# drivers_SCH.net
KiCad netlist of a schematic drawn in Altium Designer
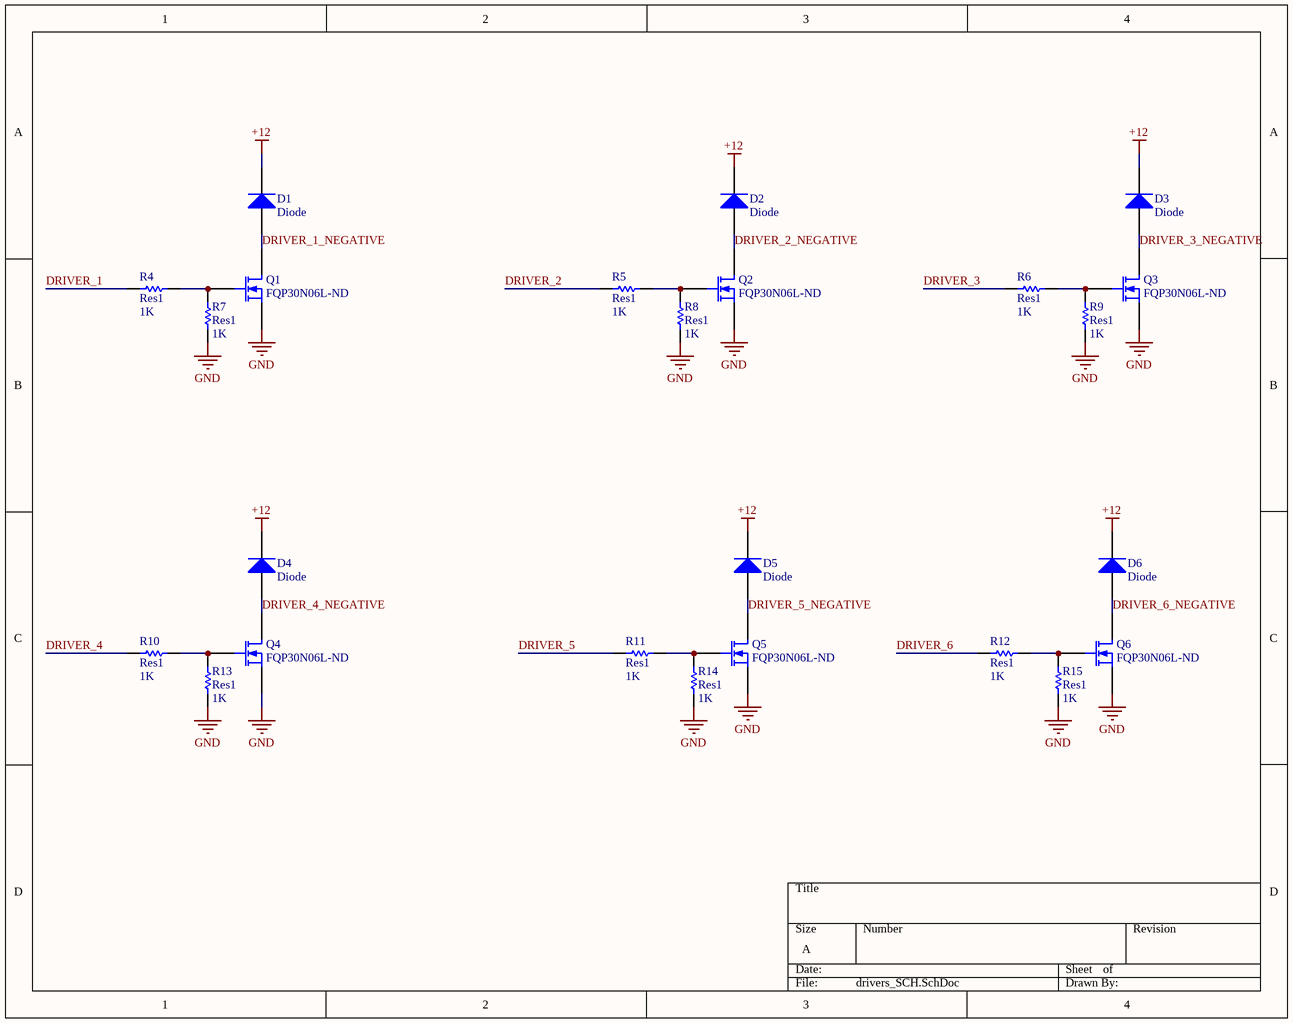
[diagram p0: drivers_SCH.SchDoc]

(export (version "E")
  (design (tool "Eeschema 10.0.6"))
  (components
    (comp (ref "D1")
      (value "Diode")
      (footprint "DIOC2012X06N")
      (description "Default Diode")
      (fields (field (name "PUBLISHER") "Altium Limited"))
      (libsource (lib "Miscellaneous Devices") (part "Diode"))
    )
    (comp (ref "D2")
      (value "Diode")
      (footprint "DIOC2012X06N")
      (description "Default Diode")
      (fields (field (name "PUBLISHER") "Altium Limited"))
      (libsource (lib "Miscellaneous Devices") (part "Diode"))
    )
    (comp (ref "D3")
      (value "Diode")
      (footprint "DIOC2012X06N")
      (description "Default Diode")
      (fields (field (name "PUBLISHER") "Altium Limited"))
      (libsource (lib "Miscellaneous Devices") (part "Diode"))
    )
    (comp (ref "D4")
      (value "Diode")
      (footprint "DIOC2012X06N")
      (description "Default Diode")
      (fields (field (name "PUBLISHER") "Altium Limited"))
      (libsource (lib "Miscellaneous Devices") (part "Diode"))
    )
    (comp (ref "D5")
      (value "Diode")
      (footprint "DIOC2012X06N")
      (description "Default Diode")
      (fields (field (name "PUBLISHER") "Altium Limited"))
      (libsource (lib "Miscellaneous Devices") (part "Diode"))
    )
    (comp (ref "D6")
      (value "Diode")
      (footprint "DIOC2012X06N")
      (description "Default Diode")
      (fields (field (name "PUBLISHER") "Altium Limited"))
      (libsource (lib "Miscellaneous Devices") (part "Diode"))
    )
    (comp (ref "Q1")
      (value "FQP30N06L-ND")
      (footprint "UA78M")
      (description "N-Channel MOSFET")
      (fields (field (name "PUBLISHER") "Altium Limited"))
      (libsource (lib "Miscellaneous Devices") (part "MOSFET-N"))
    )
    (comp (ref "Q2")
      (value "FQP30N06L-ND")
      (footprint "UA78M")
      (description "N-Channel MOSFET")
      (fields (field (name "PUBLISHER") "Altium Limited"))
      (libsource (lib "Miscellaneous Devices") (part "MOSFET-N"))
    )
    (comp (ref "Q3")
      (value "FQP30N06L-ND")
      (footprint "UA78M")
      (description "N-Channel MOSFET")
      (fields (field (name "PUBLISHER") "Altium Limited"))
      (libsource (lib "Miscellaneous Devices") (part "MOSFET-N"))
    )
    (comp (ref "Q4")
      (value "FQP30N06L-ND")
      (footprint "UA78M")
      (description "N-Channel MOSFET")
      (fields (field (name "PUBLISHER") "Altium Limited"))
      (libsource (lib "Miscellaneous Devices") (part "MOSFET-N"))
    )
    (comp (ref "Q5")
      (value "FQP30N06L-ND")
      (footprint "UA78M")
      (description "N-Channel MOSFET")
      (fields (field (name "PUBLISHER") "Altium Limited"))
      (libsource (lib "Miscellaneous Devices") (part "MOSFET-N"))
    )
    (comp (ref "Q6")
      (value "FQP30N06L-ND")
      (footprint "UA78M")
      (description "N-Channel MOSFET")
      (fields (field (name "PUBLISHER") "Altium Limited"))
      (libsource (lib "Miscellaneous Devices") (part "MOSFET-N"))
    )
    (comp (ref "R4")
      (value "Res1")
      (footprint "RESC_0805_2012")
      (description "Resistor")
      (fields (field (name "ALTIUM_VALUE") "1K") (field (name "PUBLISHER") "Altium Limited"))
      (libsource (lib "Miscellaneous Devices") (part "Res1"))
    )
    (comp (ref "R5")
      (value "Res1")
      (footprint "RESC_0805_2012")
      (description "Resistor")
      (fields (field (name "ALTIUM_VALUE") "1K") (field (name "PUBLISHER") "Altium Limited"))
      (libsource (lib "Miscellaneous Devices") (part "Res1"))
    )
    (comp (ref "R6")
      (value "Res1")
      (footprint "RESC_0805_2012")
      (description "Resistor")
      (fields (field (name "ALTIUM_VALUE") "1K") (field (name "PUBLISHER") "Altium Limited"))
      (libsource (lib "Miscellaneous Devices") (part "Res1"))
    )
    (comp (ref "R7")
      (value "Res1")
      (footprint "RESC_0805_2012")
      (description "Resistor")
      (fields (field (name "ALTIUM_VALUE") "1K") (field (name "PUBLISHER") "Altium Limited"))
      (libsource (lib "Miscellaneous Devices") (part "Res1"))
    )
    (comp (ref "R8")
      (value "Res1")
      (footprint "RESC_0805_2012")
      (description "Resistor")
      (fields (field (name "ALTIUM_VALUE") "1K") (field (name "PUBLISHER") "Altium Limited"))
      (libsource (lib "Miscellaneous Devices") (part "Res1"))
    )
    (comp (ref "R9")
      (value "Res1")
      (footprint "RESC_0805_2012")
      (description "Resistor")
      (fields (field (name "ALTIUM_VALUE") "1K") (field (name "PUBLISHER") "Altium Limited"))
      (libsource (lib "Miscellaneous Devices") (part "Res1"))
    )
    (comp (ref "R10")
      (value "Res1")
      (footprint "RESC_0805_2012")
      (description "Resistor")
      (fields (field (name "ALTIUM_VALUE") "1K") (field (name "PUBLISHER") "Altium Limited"))
      (libsource (lib "Miscellaneous Devices") (part "Res1"))
    )
    (comp (ref "R11")
      (value "Res1")
      (footprint "RESC_0805_2012")
      (description "Resistor")
      (fields (field (name "ALTIUM_VALUE") "1K") (field (name "PUBLISHER") "Altium Limited"))
      (libsource (lib "Miscellaneous Devices") (part "Res1"))
    )
    (comp (ref "R12")
      (value "Res1")
      (footprint "RESC_0805_2012")
      (description "Resistor")
      (fields (field (name "ALTIUM_VALUE") "1K") (field (name "PUBLISHER") "Altium Limited"))
      (libsource (lib "Miscellaneous Devices") (part "Res1"))
    )
    (comp (ref "R13")
      (value "Res1")
      (footprint "RESC_0805_2012")
      (description "Resistor")
      (fields (field (name "ALTIUM_VALUE") "1K") (field (name "PUBLISHER") "Altium Limited"))
      (libsource (lib "Miscellaneous Devices") (part "Res1"))
    )
    (comp (ref "R14")
      (value "Res1")
      (footprint "RESC_0805_2012")
      (description "Resistor")
      (fields (field (name "ALTIUM_VALUE") "1K") (field (name "PUBLISHER") "Altium Limited"))
      (libsource (lib "Miscellaneous Devices") (part "Res1"))
    )
    (comp (ref "R15")
      (value "Res1")
      (footprint "RESC_0805_2012")
      (description "Resistor")
      (fields (field (name "ALTIUM_VALUE") "1K") (field (name "PUBLISHER") "Altium Limited"))
      (libsource (lib "Miscellaneous Devices") (part "Res1"))
    )
  )
  (nets
    (net (code "1") (name "+12") (class "Default")
      (node (ref "D1") (pin "2") (pinfunction "K_2") (pintype "passive"))
      (node (ref "D2") (pin "2") (pinfunction "K_2") (pintype "passive"))
      (node (ref "D3") (pin "2") (pinfunction "K_2") (pintype "passive"))
      (node (ref "D4") (pin "2") (pinfunction "K_2") (pintype "passive"))
      (node (ref "D5") (pin "2") (pinfunction "K_2") (pintype "passive"))
      (node (ref "D6") (pin "2") (pinfunction "K_2") (pintype "passive"))
    )
    (net (code "2") (name "/DRIVER_1") (class "Default")
      (node (ref "R4") (pin "1") (pinfunction "1_1") (pintype "passive"))
    )
    (net (code "3") (name "/DRIVER_1_NEGATIVE") (class "Default")
      (node (ref "D1") (pin "1") (pinfunction "A_1") (pintype "passive"))
      (node (ref "Q1") (pin "2") (pinfunction "G_2") (pintype "passive"))
    )
    (net (code "4") (name "/DRIVER_2") (class "Default")
      (node (ref "R5") (pin "1") (pinfunction "1_1") (pintype "passive"))
    )
    (net (code "5") (name "/DRIVER_2_NEGATIVE") (class "Default")
      (node (ref "D2") (pin "1") (pinfunction "A_1") (pintype "passive"))
      (node (ref "Q2") (pin "2") (pinfunction "G_2") (pintype "passive"))
    )
    (net (code "6") (name "/DRIVER_3") (class "Default")
      (node (ref "R6") (pin "1") (pinfunction "1_1") (pintype "passive"))
    )
    (net (code "7") (name "/DRIVER_3_NEGATIVE") (class "Default")
      (node (ref "D3") (pin "1") (pinfunction "A_1") (pintype "passive"))
      (node (ref "Q3") (pin "2") (pinfunction "G_2") (pintype "passive"))
    )
    (net (code "8") (name "/DRIVER_4") (class "Default")
      (node (ref "R10") (pin "1") (pinfunction "1_1") (pintype "passive"))
    )
    (net (code "9") (name "/DRIVER_4_NEGATIVE") (class "Default")
      (node (ref "D4") (pin "1") (pinfunction "A_1") (pintype "passive"))
      (node (ref "Q4") (pin "2") (pinfunction "G_2") (pintype "passive"))
    )
    (net (code "10") (name "/DRIVER_5") (class "Default")
      (node (ref "R11") (pin "1") (pinfunction "1_1") (pintype "passive"))
    )
    (net (code "11") (name "/DRIVER_5_NEGATIVE") (class "Default")
      (node (ref "D5") (pin "1") (pinfunction "A_1") (pintype "passive"))
      (node (ref "Q5") (pin "2") (pinfunction "G_2") (pintype "passive"))
    )
    (net (code "12") (name "/DRIVER_6") (class "Default")
      (node (ref "R12") (pin "1") (pinfunction "1_1") (pintype "passive"))
    )
    (net (code "13") (name "/DRIVER_6_NEGATIVE") (class "Default")
      (node (ref "D6") (pin "1") (pinfunction "A_1") (pintype "passive"))
      (node (ref "Q6") (pin "2") (pinfunction "G_2") (pintype "passive"))
    )
    (net (code "14") (name "GND") (class "Default")
      (node (ref "Q1") (pin "3") (pinfunction "S_3") (pintype "passive"))
      (node (ref "Q2") (pin "3") (pinfunction "S_3") (pintype "passive"))
      (node (ref "Q3") (pin "3") (pinfunction "S_3") (pintype "passive"))
      (node (ref "Q4") (pin "3") (pinfunction "S_3") (pintype "passive"))
      (node (ref "Q5") (pin "3") (pinfunction "S_3") (pintype "passive"))
      (node (ref "Q6") (pin "3") (pinfunction "S_3") (pintype "passive"))
      (node (ref "R13") (pin "1") (pinfunction "1_1") (pintype "passive"))
      (node (ref "R14") (pin "1") (pinfunction "1_1") (pintype "passive"))
      (node (ref "R15") (pin "1") (pinfunction "1_1") (pintype "passive"))
      (node (ref "R7") (pin "1") (pinfunction "1_1") (pintype "passive"))
      (node (ref "R8") (pin "1") (pinfunction "1_1") (pintype "passive"))
      (node (ref "R9") (pin "1") (pinfunction "1_1") (pintype "passive"))
    )
    (net (code "15") (name "Net-(Q1-D)") (class "Default")
      (node (ref "Q1") (pin "1") (pinfunction "D_1") (pintype "passive"))
      (node (ref "R4") (pin "2") (pinfunction "2_2") (pintype "passive"))
      (node (ref "R7") (pin "2") (pinfunction "2_2") (pintype "passive"))
    )
    (net (code "16") (name "Net-(Q2-D)") (class "Default")
      (node (ref "Q2") (pin "1") (pinfunction "D_1") (pintype "passive"))
      (node (ref "R5") (pin "2") (pinfunction "2_2") (pintype "passive"))
      (node (ref "R8") (pin "2") (pinfunction "2_2") (pintype "passive"))
    )
    (net (code "17") (name "Net-(Q3-D)") (class "Default")
      (node (ref "Q3") (pin "1") (pinfunction "D_1") (pintype "passive"))
      (node (ref "R6") (pin "2") (pinfunction "2_2") (pintype "passive"))
      (node (ref "R9") (pin "2") (pinfunction "2_2") (pintype "passive"))
    )
    (net (code "18") (name "Net-(Q4-D)") (class "Default")
      (node (ref "Q4") (pin "1") (pinfunction "D_1") (pintype "passive"))
      (node (ref "R10") (pin "2") (pinfunction "2_2") (pintype "passive"))
      (node (ref "R13") (pin "2") (pinfunction "2_2") (pintype "passive"))
    )
    (net (code "19") (name "Net-(Q5-D)") (class "Default")
      (node (ref "Q5") (pin "1") (pinfunction "D_1") (pintype "passive"))
      (node (ref "R11") (pin "2") (pinfunction "2_2") (pintype "passive"))
      (node (ref "R14") (pin "2") (pinfunction "2_2") (pintype "passive"))
    )
    (net (code "20") (name "Net-(Q6-D)") (class "Default")
      (node (ref "Q6") (pin "1") (pinfunction "D_1") (pintype "passive"))
      (node (ref "R12") (pin "2") (pinfunction "2_2") (pintype "passive"))
      (node (ref "R15") (pin "2") (pinfunction "2_2") (pintype "passive"))
    )
  )
)
